# 12_5_3v3_Converters.net
KiCad netlist of a schematic drawn in Altium Designer
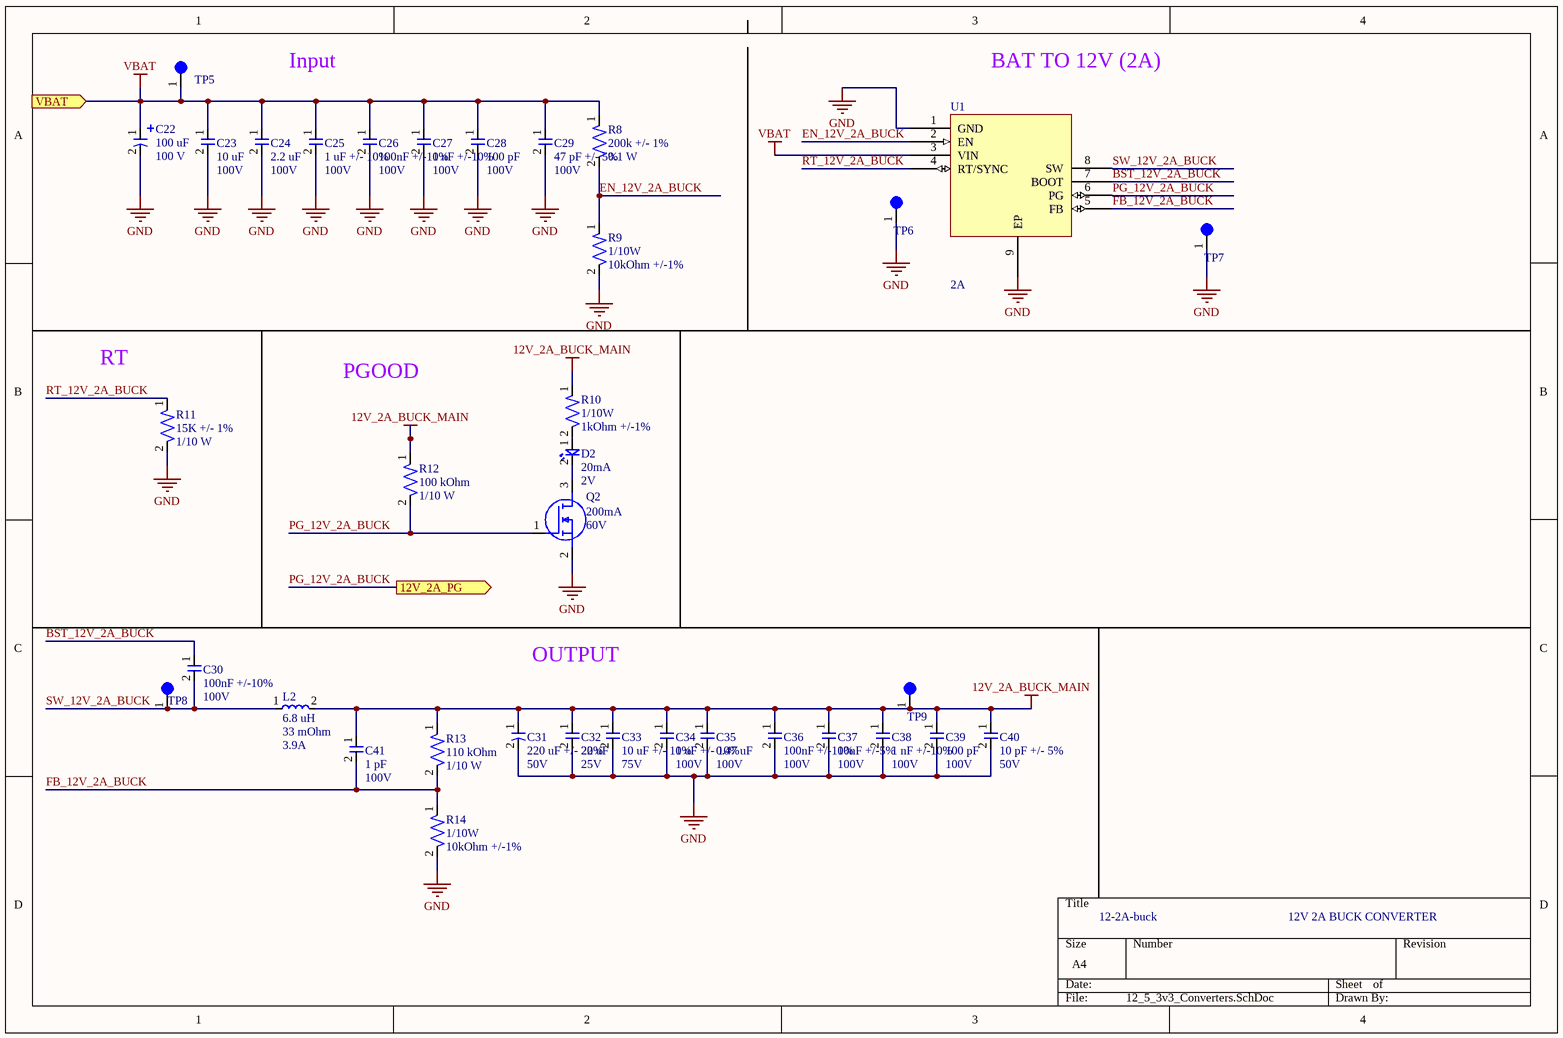
[diagram p0: 12_5_3v3_Converters.SchDoc]

(export (version "E")
  (design (tool "Eeschema 10.0.6"))
  (components
    (comp (ref "C22")
      (value "100SEV100M12.5X16")
      (footprint "ELEC-100U-0001")
      (description "100 µF 100 V Aluminum Electrolytic Capacitors Radial, Can - SMD 2000 Hrs @ 85°C")
      (fields
        (field (name "MANUFACTURER") "Rubycon")
        (field (name "TOLERANCE") "+/- 20%")
        (field (name "CAPACITANCE") "100 uF")
        (field (name "VOLTAGE") "100 V")
      )
      (libsource (lib "MasterLib") (part "ELEC-100U-0001"))
    )
    (comp (ref "C23")
      (value "GRM32EC72A106KE05L")
      (footprint "CAP-1210")
      (description "10 µF ±10% 100V Ceramic Capacitor X7S 1210 (3225 Metric)")
      (fields (field (name "CAPCITANCE") "10 uF") (field (name "VOLTAGE RATING") "100V"))
      (libsource (lib "MasterLib") (part "CAP-10U-0003"))
    )
    (comp (ref "C24")
      (value "CL31B225KCHSNNE")
      (footprint "CAP-1206")
      (description "2.2 µF ±10% 100V Ceramic Capacitor X7R 1206 (3216 Metric)")
      (fields
        (field (name "MANUFACTURER") "Samsung Electro-Mechanics")
        (field (name "TOLERANCE") "+/- 10%")
        (field (name "CAPACITANCE") "2.2 uF")
        (field (name "VOLTAGE") "100V")
      )
      (libsource (lib "MasterLib") (part "CAP-2.2U-0003"))
    )
    (comp (ref "C25")
      (value "CL31B105KCHNNNE")
      (footprint "CAP-1206 - duplicate")
      (description "1 µF ±10% 100V Ceramic Capacitor X7R 1206 (3216 Metric)")
      (fields (field (name "CAPACITANCE") "1 uF +/- 10%") (field (name "VOLTAGE") "100V"))
      (libsource (lib "MasterLib") (part "CAP-1U-0001"))
    )
    (comp (ref "C26")
      (value "CC0603KRX7R0BB104")
      (footprint "CAP-0603")
      (description "CAP CER 0.1UF 100V X7R 0603")
      (fields
        (field (name "MANUFACTURER") "YAGEO")
        (field (name "CAPACITANCE") "100nF +/-10%")
        (field (name "VOLTAGE RATING") "100V")
      )
      (libsource (lib "MasterLib") (part "CAP-100N-0001"))
    )
    (comp (ref "C27")
      (value "C0603Y102K1RAC7867")
      (footprint "CAP-0603")
      (description "1000 pF ±10% 100V Ceramic Capacitor X7R 0603 (1608 Metric)")
      (fields (field (name "CAPACITANCE") "1 nF +/-10%") (field (name "VOLTAGE") "100V"))
      (libsource (lib "MasterLib") (part "CAP-1N-0001"))
    )
    (comp (ref "C28")
      (value "0603N101J101CT")
      (footprint "CAP-0603")
      (description "100 pF ±5% 100V Ceramic Capacitor C0G, NP0 0603 (1608 Metric)")
      (fields
        (field (name "TOLERANCE") "+/-5%")
        (field (name "CAPACITANCE") "100 pF")
        (field (name "VOLTAGE") "100V")
      )
      (libsource (lib "MasterLib") (part "CAP-100P-0002"))
    )
    (comp (ref "C29")
      (value "7447798111")
      (footprint "CAP-0603")
      (description "47 pF ±5% 100V Ceramic Capacitor C0G, NP0 0603 (1608 Metric)")
      (fields (field (name "CAPACITANCE") "47 pF +/- 5%") (field (name "VOLTAGE RATING") "100V"))
      (libsource (lib "MasterLib") (part "CAP-47P-0001"))
    )
    (comp (ref "C30")
      (value "CC0603KRX7R0BB104")
      (footprint "CAP-0603")
      (description "CAP CER 0.1UF 100V X7R 0603")
      (fields
        (field (name "MANUFACTURER") "YAGEO")
        (field (name "CAPACITANCE") "100nF +/-10%")
        (field (name "VOLTAGE RATING") "100V")
      )
      (libsource (lib "MasterLib") (part "CAP-100N-0001"))
    )
    (comp (ref "C31")
      (value "50TZV220M10X10.5")
      (footprint "ELEC-220U-0003")
      (description "220 µF 50 V Aluminum Electrolytic Capacitors Radial, Can - SMD 2000 Hrs @ 105°C")
      (fields (field (name "CAPACITANCE") "220 uF +/- 20%") (field (name "VOLTAGE RATING") "50V"))
      (libsource (lib "MasterLib") (part "ELEC-220U-0003"))
    )
    (comp (ref "C32")
      (value "CL32B226KAJNNNE")
      (footprint "CAP-1210")
      (description "22 µF ±10% 25V Ceramic Capacitor X7R 1210 (3225 Metric)")
      (fields
        (field (name "TOLERANCE") "+/- 10%")
        (field (name "CAPACITANCE") "22 uF")
        (field (name "VOLTAGE") "25V")
      )
      (libsource (lib "MasterLib") (part "CAP-22U-0003"))
    )
    (comp (ref "C33")
      (value "C3225X7R1N106K250AC")
      (footprint "CAP-1210")
      (description "10 µF ±10% 75V Ceramic Capacitor X7R 1210 (3225 Metric)")
      (fields (field (name "CAPACITANCE") "10 uF +/- 10%") (field (name "VOLTAGE RATING") "75V"))
      (libsource (lib "MasterLib") (part "CAP-10U-0004"))
    )
    (comp (ref "C34")
      (value "CL31B105KCHNNNE")
      (footprint "CAP-1206 - duplicate")
      (description "1 µF ±10% 100V Ceramic Capacitor X7R 1206 (3216 Metric)")
      (fields (field (name "CAPACITANCE") "1 uF +/- 10%") (field (name "VOLTAGE") "100V"))
      (libsource (lib "MasterLib") (part "CAP-1U-0001"))
    )
    (comp (ref "C35")
      (value "KAM21KR72A474KL")
      (footprint "CAP-0805")
      (description "0.47 µF ±10% 100V Ceramic Capacitor X7R 0805 (2012 Metric)")
      (fields
        (field (name "TOLERANCE") "+/- 10%")
        (field (name "CAPACITANCE") "0.47 uF")
        (field (name "VOLTAGE") "100V")
      )
      (libsource (lib "MasterLib") (part "CAP-0.47U-0001"))
    )
    (comp (ref "C36")
      (value "CC0603KRX7R0BB104")
      (footprint "CAP-0603")
      (description "CAP CER 0.1UF 100V X7R 0603")
      (fields
        (field (name "MANUFACTURER") "YAGEO")
        (field (name "CAPACITANCE") "100nF +/-10%")
        (field (name "VOLTAGE RATING") "100V")
      )
      (libsource (lib "MasterLib") (part "CAP-100N-0001"))
    )
    (comp (ref "C37")
      (value "C1608C0G2A103J080AC")
      (footprint "CAP-0603")
      (description "CAP CER 10000PF 100V C0G 0603")
      (fields
        (field (name "MANUFACTURER") "TDK Corporation")
        (field (name "CAPACITANCE") "10nF +/-5%")
        (field (name "VOLTAGE RATING") "100V")
      )
      (libsource (lib "MasterLib") (part "CAP-10N-0002"))
    )
    (comp (ref "C38")
      (value "C0603Y102K1RAC7867")
      (footprint "CAP-0603")
      (description "1000 pF ±10% 100V Ceramic Capacitor X7R 0603 (1608 Metric)")
      (fields (field (name "CAPACITANCE") "1 nF +/-10%") (field (name "VOLTAGE") "100V"))
      (libsource (lib "MasterLib") (part "CAP-1N-0001"))
    )
    (comp (ref "C39")
      (value "0603N101J101CT")
      (footprint "CAP-0603")
      (description "100 pF ±5% 100V Ceramic Capacitor C0G, NP0 0603 (1608 Metric)")
      (fields
        (field (name "TOLERANCE") "+/-5%")
        (field (name "CAPACITANCE") "100 pF")
        (field (name "VOLTAGE") "100V")
      )
      (libsource (lib "MasterLib") (part "CAP-100P-0002"))
    )
    (comp (ref "C40")
      (value "0603N100J500CT")
      (footprint "CAP-0603")
      (description "10 pF ±5% 50V Ceramic Capacitor C0G, NP0 0603 (1608 Metric)")
      (fields
        (field (name "MANUFACTURER") "Walshin Technology Corporation")
        (field (name "CAPACITANCE") "10 pF +/- 5%")
        (field (name "VOLTAGE RATING") "50V")
      )
      (libsource (lib "MasterLib") (part "CAP-10P-0001"))
    )
    (comp (ref "C41")
      (value "885012006087")
      (footprint "CAP-0603")
      (description "1 pF ±0.25pF 100V Ceramic Capacitor C0G, NP0 0603 (1608 Metric)")
      (fields
        (field (name "TOLERANCE") "+/- 0.25 pF")
        (field (name "CAPACITANCE") "1 pF")
        (field (name "VOLTAGE") "100V")
      )
      (libsource (lib "MasterLib") (part "CAP-1P-0001"))
    )
    (comp (ref "D2")
      (value "150060AS75000")
      (footprint "LED-0603")
      (description "CAP CER 0.1UF 100V X7R 0603")
      (fields
        (field (name "MANUFACTURER") "Wurth Electronik")
        (field (name "CURRENT RATING") "20mA")
        (field (name "VF") "2V")
      )
      (libsource (lib "MasterLib") (part "LED_Amber_0001"))
    )
    (comp (ref "L2")
      (value "SRN8040-6R8Y")
      (footprint "PWRIND-6.8U-0001")
      (description "6.8 µH Semi-Shielded Drum Core, Wirewound Inductor 3.9 A 33mOhm Max Nonstandard")
      (fields
        (field (name "TOLERANCE") "30%")
        (field (name "INDUCTANCE") "6.8 uH")
        (field (name "DCR") "33 mOhm")
        (field (name "DCI") "3.9A")
      )
      (libsource (lib "MasterLib") (part "PWRIND-6.8U-0001"))
    )
    (comp (ref "Q2")
      (value "T2N7002AK,LM")
      (footprint "NMOS-SOT23-3")
      (description "MOSFET N-CH 60V 200MA SOT23")
      (fields
        (field (name "MANUFACTURER") "Toshiba")
        (field (name "ID-CONTINUOUS") "200mA")
        (field (name "VDS-MAX") "60V")
      )
      (libsource (lib "MasterLib") (part "NMOS-200MA-0001"))
    )
    (comp (ref "R8")
      (value "ERJ-3EKF2003V")
      (footprint "RES-0603")
      (description "200 kOhms ±1% 0.1W, 1/10W Chip Resistor 0603 (1608 Metric) Automotive AEC-Q200 Thick Film")
      (fields
        (field (name "MANUFACTURER") "Panasonic Electronic Components")
        (field (name "RESISTANCE") "200k +/- 1%")
        (field (name "POWER RATING") "0.1 W")
      )
      (libsource (lib "MasterLib") (part "RES-200K-0001"))
    )
    (comp (ref "R9")
      (value "RC0603FR-0710KP")
      (footprint "RES-0603")
      (description "RES SMD 10K OHM 1% 1/10W 0603")
      (fields
        (field (name "MANUFACTURER") "YAGEO")
        (field (name "POWER RATING") "1/10W")
        (field (name "RESISTANCE") "10kOhm +/-1%")
      )
      (libsource (lib "MasterLib") (part "RES-10K-0002"))
    )
    (comp (ref "R10")
      (value "RT0603FRE131KL")
      (footprint "RES-0603")
      (description "1 kOhms ±1% 0.1W, 1/10W Chip Resistor 0603 (1608 Metric) Thin Film")
      (fields
        (field (name "MANUFACTURER") "YAGEO")
        (field (name "POWER RATING") "1/10W")
        (field (name "RESISTANCE") "1kOhm +/-1%")
      )
      (libsource (lib "MasterLib") (part "RES-1K-0002"))
    )
    (comp (ref "R11")
      (value "ERJ-2RKF1502X")
      (footprint "RES-0402")
      (description "15 kOhms ±1% 0.1W, 1/10W Chip Resistor 0402 (1005 Metric) Automotive AEC-Q200 Thick Film")
      (fields (field (name "RES") "15K +/- 1%") (field (name "POWER") "1/10 W"))
      (libsource (lib "MasterLib") (part "RES-15K-0001"))
    )
    (comp (ref "R12")
      (value "RC0603FR-07100KL")
      (footprint "RES-0603")
      (description "100 kOhms ±1% 0.1W, 1/10W Chip Resistor 0603 (1608 Metric) Moisture Resistant Thick Film")
      (fields
        (field (name "TOLERANCE") "+/- 1%")
        (field (name "RESISTANCE") "100 kOhm")
        (field (name "POWER") "1/10 W")
      )
      (libsource (lib "MasterLib") (part "RES-100K-0003"))
    )
    (comp (ref "R13")
      (value "RC0603FR-07110KL")
      (footprint "RES-0603")
      (description "110 kOhms ±1% 0.1W, 1/10W Chip Resistor 0603 (1608 Metric) Moisture Resistant Thick Film")
      (fields
        (field (name "TOLERANCE") "+/- 1%")
        (field (name "RESISTANCE") "110 kOhm")
        (field (name "POWER") "1/10 W")
      )
      (libsource (lib "MasterLib") (part "RES-110K-0001"))
    )
    (comp (ref "R14")
      (value "RC0603FR-0710KP")
      (footprint "RES-0603")
      (description "RES SMD 10K OHM 1% 1/10W 0603")
      (fields
        (field (name "MANUFACTURER") "YAGEO")
        (field (name "POWER RATING") "1/10W")
        (field (name "RESISTANCE") "10kOhm +/-1%")
      )
      (libsource (lib "MasterLib") (part "RES-10K-0002"))
    )
    (comp (ref "TP5")
      (value "5003")
      (footprint "TEST-POINT-0001")
      (description "Oranange PC Test Point, Miniature Phoisphor Bronze Silver Plating Through Hole Mounting Type")
      (libsource (lib "MasterLib") (part "TEST-POINT-0001"))
    )
    (comp (ref "TP6")
      (value "5003")
      (footprint "TEST-POINT-0001")
      (description "Oranange PC Test Point, Miniature Phoisphor Bronze Silver Plating Through Hole Mounting Type")
      (libsource (lib "MasterLib") (part "TEST-POINT-0001"))
    )
    (comp (ref "TP7")
      (value "5003")
      (footprint "TEST-POINT-0001")
      (description "Oranange PC Test Point, Miniature Phoisphor Bronze Silver Plating Through Hole Mounting Type")
      (libsource (lib "MasterLib") (part "TEST-POINT-0001"))
    )
    (comp (ref "TP8")
      (value "5003")
      (footprint "TEST-POINT-0001")
      (description "Oranange PC Test Point, Miniature Phoisphor Bronze Silver Plating Through Hole Mounting Type")
      (libsource (lib "MasterLib") (part "TEST-POINT-0001"))
    )
    (comp (ref "TP9")
      (value "5003")
      (footprint "TEST-POINT-0001")
      (description "Oranange PC Test Point, Miniature Phoisphor Bronze Silver Plating Through Hole Mounting Type")
      (libsource (lib "MasterLib") (part "TEST-POINT-0001"))
    )
    (comp (ref "U1")
      (value "LMR38020SDDAR")
      (footprint "IC-8PowerSOIC")
      (description "Buck Switching Regulator IC Positive Adjustable 1V 1 Output 2A 8-PowerSOIC (0.154\", 3.90mm Width)")
      (fields (field (name "CURRENT") "2A"))
      (libsource (lib "MasterLib") (part "IC-BUCK-0007"))
    )
  )
  (nets
    (net (code "1") (name "/BST_12V_2A_BUCK") (class "Default")
      (node (ref "C30") (pin "1") (pinfunction "1_1") (pintype "passive"))
      (node (ref "U1") (pin "7") (pinfunction "BOOT_7") (pintype "power_in"))
    )
    (net (code "2") (name "/EN_12V_2A_BUCK") (class "Default")
      (node (ref "R8") (pin "2") (pinfunction "2_2") (pintype "passive"))
      (node (ref "R9") (pin "1") (pinfunction "1_1") (pintype "passive"))
      (node (ref "U1") (pin "2") (pinfunction "EN_2") (pintype "input"))
    )
    (net (code "3") (name "/FB_12V_2A_BUCK") (class "Default")
      (node (ref "C41") (pin "2") (pinfunction "2_2") (pintype "passive"))
      (node (ref "R13") (pin "2") (pinfunction "2_2") (pintype "passive"))
      (node (ref "R14") (pin "1") (pinfunction "1_1") (pintype "passive"))
      (node (ref "U1") (pin "5") (pinfunction "FB_5") (pintype "bidirectional"))
    )
    (net (code "4") (name "/PG_12V_2A_BUCK") (class "Default")
      (node (ref "Q2") (pin "1") (pinfunction "G_1") (pintype "passive"))
      (node (ref "R12") (pin "2") (pinfunction "2_2") (pintype "passive"))
      (node (ref "U1") (pin "6") (pinfunction "PG_6") (pintype "bidirectional"))
    )
    (net (code "5") (name "/RT_12V_2A_BUCK") (class "Default")
      (node (ref "R11") (pin "1") (pinfunction "1_1") (pintype "passive"))
      (node (ref "U1") (pin "4") (pinfunction "RT/SYNC_4") (pintype "bidirectional"))
    )
    (net (code "6") (name "/SW_12V_2A_BUCK") (class "Default")
      (node (ref "C30") (pin "2") (pinfunction "2_2") (pintype "passive"))
      (node (ref "L2") (pin "1") (pinfunction "1_1") (pintype "passive"))
      (node (ref "TP8") (pin "1") (pinfunction "0_1") (pintype "passive"))
      (node (ref "U1") (pin "8") (pinfunction "SW_8") (pintype "power_in"))
    )
    (net (code "7") (name "12V_2A_BUCK_MAIN") (class "Default")
      (node (ref "C31") (pin "1") (pinfunction "1_1") (pintype "passive"))
      (node (ref "C32") (pin "1") (pinfunction "1_1") (pintype "passive"))
      (node (ref "C33") (pin "1") (pinfunction "1_1") (pintype "passive"))
      (node (ref "C34") (pin "1") (pinfunction "1_1") (pintype "passive"))
      (node (ref "C35") (pin "1") (pinfunction "1_1") (pintype "passive"))
      (node (ref "C36") (pin "1") (pinfunction "1_1") (pintype "passive"))
      (node (ref "C37") (pin "1") (pinfunction "1_1") (pintype "passive"))
      (node (ref "C38") (pin "1") (pinfunction "1_1") (pintype "passive"))
      (node (ref "C39") (pin "1") (pinfunction "1_1") (pintype "passive"))
      (node (ref "C40") (pin "1") (pinfunction "1_1") (pintype "passive"))
      (node (ref "C41") (pin "1") (pinfunction "1_1") (pintype "passive"))
      (node (ref "L2") (pin "2") (pinfunction "2_2") (pintype "passive"))
      (node (ref "R10") (pin "1") (pinfunction "1_1") (pintype "passive"))
      (node (ref "R12") (pin "1") (pinfunction "1_1") (pintype "passive"))
      (node (ref "R13") (pin "1") (pinfunction "1_1") (pintype "passive"))
      (node (ref "TP9") (pin "1") (pinfunction "0_1") (pintype "passive"))
    )
    (net (code "8") (name "GND") (class "Default")
      (node (ref "C22") (pin "2") (pinfunction "2_2") (pintype "passive"))
      (node (ref "C23") (pin "2") (pinfunction "2_2") (pintype "passive"))
      (node (ref "C24") (pin "2") (pinfunction "2_2") (pintype "passive"))
      (node (ref "C25") (pin "2") (pinfunction "2_2") (pintype "passive"))
      (node (ref "C26") (pin "2") (pinfunction "2_2") (pintype "passive"))
      (node (ref "C27") (pin "2") (pinfunction "2_2") (pintype "passive"))
      (node (ref "C28") (pin "2") (pinfunction "2_2") (pintype "passive"))
      (node (ref "C29") (pin "2") (pinfunction "2_2") (pintype "passive"))
      (node (ref "C31") (pin "2") (pinfunction "2_2") (pintype "passive"))
      (node (ref "C32") (pin "2") (pinfunction "2_2") (pintype "passive"))
      (node (ref "C33") (pin "2") (pinfunction "2_2") (pintype "passive"))
      (node (ref "C34") (pin "2") (pinfunction "2_2") (pintype "passive"))
      (node (ref "C35") (pin "2") (pinfunction "2_2") (pintype "passive"))
      (node (ref "C36") (pin "2") (pinfunction "2_2") (pintype "passive"))
      (node (ref "C37") (pin "2") (pinfunction "2_2") (pintype "passive"))
      (node (ref "C38") (pin "2") (pinfunction "2_2") (pintype "passive"))
      (node (ref "C39") (pin "2") (pinfunction "2_2") (pintype "passive"))
      (node (ref "C40") (pin "2") (pinfunction "2_2") (pintype "passive"))
      (node (ref "Q2") (pin "2") (pinfunction "S_2") (pintype "passive"))
      (node (ref "R11") (pin "2") (pinfunction "2_2") (pintype "passive"))
      (node (ref "R14") (pin "2") (pinfunction "2_2") (pintype "passive"))
      (node (ref "R9") (pin "2") (pinfunction "2_2") (pintype "passive"))
      (node (ref "TP6") (pin "1") (pinfunction "0_1") (pintype "passive"))
      (node (ref "TP7") (pin "1") (pinfunction "0_1") (pintype "passive"))
      (node (ref "U1") (pin "1") (pinfunction "GND_1") (pintype "power_in"))
      (node (ref "U1") (pin "9") (pinfunction "EP_9") (pintype "power_in"))
    )
    (net (code "9") (name "Net-(D2-Pad1)") (class "Default")
      (node (ref "D2") (pin "1") (pinfunction "1_1") (pintype "passive"))
      (node (ref "R10") (pin "2") (pinfunction "2_2") (pintype "passive"))
    )
    (net (code "10") (name "Net-(Q2-D)") (class "Default")
      (node (ref "D2") (pin "2") (pinfunction "2_2") (pintype "passive"))
      (node (ref "Q2") (pin "3") (pinfunction "D_3") (pintype "passive"))
    )
    (net (code "11") (name "VBAT") (class "Default")
      (node (ref "C22") (pin "1") (pinfunction "1_1") (pintype "passive"))
      (node (ref "C23") (pin "1") (pinfunction "1_1") (pintype "passive"))
      (node (ref "C24") (pin "1") (pinfunction "1_1") (pintype "passive"))
      (node (ref "C25") (pin "1") (pinfunction "1_1") (pintype "passive"))
      (node (ref "C26") (pin "1") (pinfunction "1_1") (pintype "passive"))
      (node (ref "C27") (pin "1") (pinfunction "1_1") (pintype "passive"))
      (node (ref "C28") (pin "1") (pinfunction "1_1") (pintype "passive"))
      (node (ref "C29") (pin "1") (pinfunction "1_1") (pintype "passive"))
      (node (ref "R8") (pin "1") (pinfunction "1_1") (pintype "passive"))
      (node (ref "TP5") (pin "1") (pinfunction "0_1") (pintype "passive"))
      (node (ref "U1") (pin "3") (pinfunction "VIN_3") (pintype "power_in"))
    )
  )
)
